# esp_wifi_switch.net
KiCad netlist of a schematic drawn in EAGLE
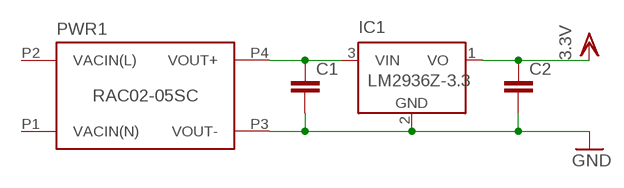
[diagram p0: schematic, sheet 1]

(export (version "E")
  (design (tool "Eeschema 10.0.6"))
  (components
    (comp (ref "C1")
      (value "C-EU025-025X050")
      (footprint "eagle-import:C025-025X050")
      (libsource (lib "eagle-import") (part "C-EU025-025X050"))
    )
    (comp (ref "C2")
      (value "C-EU025-025X050")
      (footprint "eagle-import:C025-025X050")
      (libsource (lib "eagle-import") (part "C-EU025-025X050"))
    )
    (comp (ref "IC1")
      (value "LM2936Z-3.3")
      (footprint "eagle-import:TO92")
      (fields (field (name "MF") "NATIONAL SEMICONDUCTOR") (field (name "MPN") "LM2936Z-3.3/NOPB"))
      (libsource (lib "eagle-import") (part "LM2936?Z-3.3"))
    )
    (comp (ref "PWR1")
      (value "RAC02-05SC")
      (footprint "eagle-import:LOW_PROFILE_POWER_MODULE")
      (libsource (lib "eagle-import") (part "RACSC02-05"))
    )
  )
  (nets
    (net (code "1") (name "/VACIN(L)") (class "Default")
      (node (ref "PWR1") (pin "P2") (pinfunction "VACIN(L)_P2") (pintype "power_in"))
    )
    (net (code "2") (name "/VACIN(N)") (class "Default")
      (node (ref "PWR1") (pin "P1") (pinfunction "VACIN(N)_P1") (pintype "power_in"))
    )
    (net (code "3") (name "3.3V") (class "Default")
      (node (ref "C2") (pin "1") (pinfunction "1_1") (pintype "passive"))
      (node (ref "IC1") (pin "1") (pinfunction "VO_1") (pintype "passive"))
    )
    (net (code "4") (name "GND") (class "Default")
      (node (ref "C1") (pin "2") (pinfunction "2_2") (pintype "passive"))
      (node (ref "C2") (pin "2") (pinfunction "2_2") (pintype "passive"))
      (node (ref "IC1") (pin "2") (pinfunction "GND_2") (pintype "passive"))
      (node (ref "PWR1") (pin "P3") (pinfunction "VOUT-_P3") (pintype "power_in"))
    )
    (net (code "5") (name "Net-(IC1-VIN)") (class "Default")
      (node (ref "C1") (pin "1") (pinfunction "1_1") (pintype "passive"))
      (node (ref "IC1") (pin "3") (pinfunction "VIN_3") (pintype "input"))
      (node (ref "PWR1") (pin "P4") (pinfunction "VOUT+_P4") (pintype "power_in"))
    )
  )
)
